# SH6_-_MICROCONTROLLER.net
KiCad netlist of a schematic drawn in Altium Designer
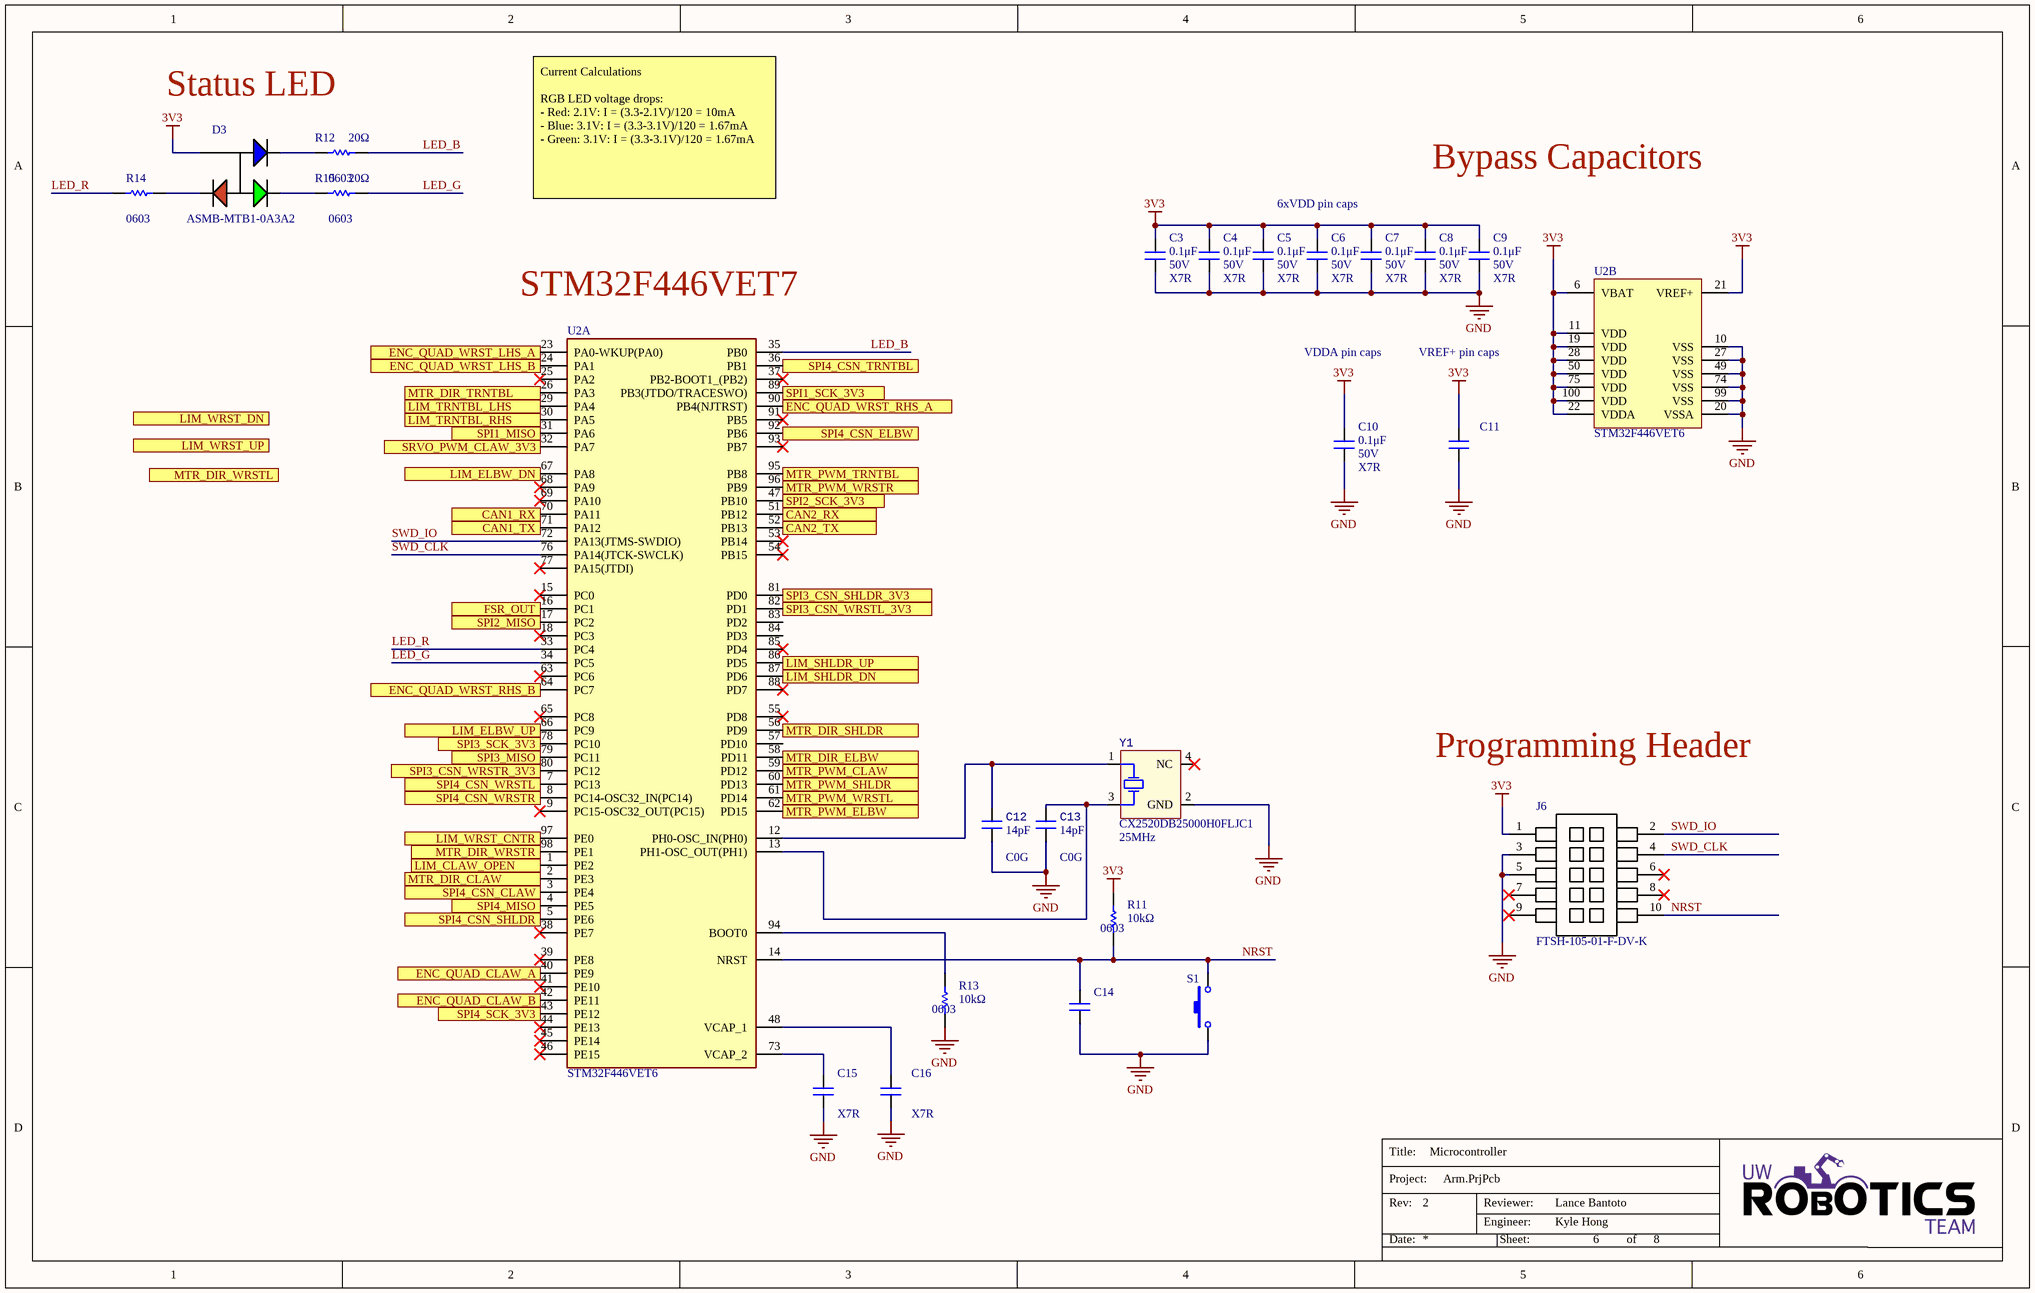
[diagram p0: SH6 - MICROCONTROLLER.SchDoc]

(export (version "E")
  (design (tool "Eeschema 10.0.6"))
  (components
    (comp (ref "C3")
      (value "0.1μF")
      (footprint "CAP0603")
      (description "CAP CER 0.1UF 50V X7R 0603")
      (fields
        (field (name "VOLTAGE RATING") "50V")
        (field (name "DIELECTRIC") "X7R")
        (field (name "Comment") "CAP_0.1uF_50V_0603")
      )
      (libsource (lib "UWRT_Schematic_Library_2020") (part "CAP_0.1uF_50V_0603"))
    )
    (comp (ref "C4")
      (value "0.1μF")
      (footprint "CAP0603")
      (description "CAP CER 0.1UF 50V X7R 0603")
      (fields
        (field (name "VOLTAGE RATING") "50V")
        (field (name "DIELECTRIC") "X7R")
        (field (name "Comment") "CAP_0.1uF_50V_0603")
      )
      (libsource (lib "UWRT_Schematic_Library_2020") (part "CAP_0.1uF_50V_0603"))
    )
    (comp (ref "C5")
      (value "0.1μF")
      (footprint "CAP0603")
      (description "CAP CER 0.1UF 50V X7R 0603")
      (fields
        (field (name "VOLTAGE RATING") "50V")
        (field (name "DIELECTRIC") "X7R")
        (field (name "Comment") "CAP_0.1uF_50V_0603")
      )
      (libsource (lib "UWRT_Schematic_Library_2020") (part "CAP_0.1uF_50V_0603"))
    )
    (comp (ref "C6")
      (value "0.1μF")
      (footprint "CAP0603")
      (description "CAP CER 0.1UF 50V X7R 0603")
      (fields
        (field (name "VOLTAGE RATING") "50V")
        (field (name "DIELECTRIC") "X7R")
        (field (name "Comment") "CAP_0.1uF_50V_0603")
      )
      (libsource (lib "UWRT_Schematic_Library_2020") (part "CAP_0.1uF_50V_0603"))
    )
    (comp (ref "C7")
      (value "0.1μF")
      (footprint "CAP0603")
      (description "CAP CER 0.1UF 50V X7R 0603")
      (fields
        (field (name "VOLTAGE RATING") "50V")
        (field (name "DIELECTRIC") "X7R")
        (field (name "Comment") "CAP_0.1uF_50V_0603")
      )
      (libsource (lib "UWRT_Schematic_Library_2020") (part "CAP_0.1uF_50V_0603"))
    )
    (comp (ref "C8")
      (value "0.1μF")
      (footprint "CAP0603")
      (description "CAP CER 0.1UF 50V X7R 0603")
      (fields
        (field (name "VOLTAGE RATING") "50V")
        (field (name "DIELECTRIC") "X7R")
        (field (name "Comment") "CAP_0.1uF_50V_0603")
      )
      (libsource (lib "UWRT_Schematic_Library_2020") (part "CAP_0.1uF_50V_0603"))
    )
    (comp (ref "C9")
      (value "0.1μF")
      (footprint "CAP0603")
      (description "CAP CER 0.1UF 50V X7R 0603")
      (fields
        (field (name "VOLTAGE RATING") "50V")
        (field (name "DIELECTRIC") "X7R")
        (field (name "Comment") "CAP_0.1uF_50V_0603")
      )
      (libsource (lib "UWRT_Schematic_Library_2020") (part "CAP_0.1uF_50V_0603"))
    )
    (comp (ref "C10")
      (value "0.1μF")
      (footprint "CAP0603")
      (description "CAP CER 0.1UF 50V X7R 0603")
      (fields
        (field (name "VOLTAGE RATING") "50V")
        (field (name "DIELECTRIC") "X7R")
        (field (name "Comment") "CAP_0.1uF_50V_0603")
      )
      (libsource (lib "UWRT_Schematic_Library_2020") (part "CAP_0.1uF_50V_0603"))
    )
    (comp (ref "C11")
      (value "CAP_1uF_25V_0603")
      (footprint "CAP0603")
      (description "CAP CER 1UF 25V X5R 0603")
      (libsource (lib "UWRT_Schematic_Library_2020") (part "CAP_1uF_25V_0603"))
    )
    (comp (ref "C12")
      (value "14pF")
      (footprint "CAP0603")
      (description "CAP CER 14PF 50V C0G/NP0 0603")
      (fields (field (name "DIELECTRIC") "C0G") (field (name "Comment") "CAP_14pF_50V_0603"))
      (libsource (lib "UWRT_Schematic_Library_2020") (part "CAP_14pF_50V_0603"))
    )
    (comp (ref "C13")
      (value "14pF")
      (footprint "CAP0603")
      (description "CAP CER 14PF 50V C0G/NP0 0603")
      (fields (field (name "DIELECTRIC") "C0G") (field (name "Comment") "CAP_14pF_50V_0603"))
      (libsource (lib "UWRT_Schematic_Library_2020") (part "CAP_14pF_50V_0603"))
    )
    (comp (ref "C14")
      (value "CAP_1uF_25V_0603")
      (footprint "CAP0603")
      (description "CAP CER 1UF 25V X5R 0603")
      (libsource (lib "UWRT_Schematic_Library_2020") (part "CAP_1uF_25V_0603"))
    )
    (comp (ref "C15")
      (value "CAP_4.7uF_50V_1206")
      (footprint "CAP1206")
      (description "CAP CER 4.7UF 50V X7R 1206")
      (fields (field (name "DIELECTRIC") "X7R"))
      (libsource (lib "UWRT_Schematic_Library_2020") (part "CAP_4.7uF_50V_1206"))
    )
    (comp (ref "C16")
      (value "CAP_4.7uF_50V_1206")
      (footprint "CAP1206")
      (description "CAP CER 4.7UF 50V X7R 1206")
      (fields (field (name "DIELECTRIC") "X7R"))
      (libsource (lib "UWRT_Schematic_Library_2020") (part "CAP_4.7uF_50V_1206"))
    )
    (comp (ref "D3")
      (value "LED_RGB")
      (footprint "LED_RGB")
      (description "LED RGB DIFFUSED 4PLCC SMD")
      (fields (field (name "MANUFACTURER PART NUMBER 1") "ASMB-MTB1-0A3A2"))
      (libsource (lib "UWRT_Schematic_Library_2020") (part "LED_RGB"))
    )
    (comp (ref "J6")
      (value "CON_PROGRAMMING")
      (footprint "FTSH-105-01-F-DV-K-P-TR")
      (description "CONN HEADER SMD 10POS 1.27MM")
      (fields (field (name "MANUFACTURER PART NUMBER 1") "FTSH-105-01-F-DV-K"))
      (libsource (lib "UWRT_Schematic_Library_2020") (part "CON_PROGRAMMING"))
    )
    (comp (ref "R11")
      (value "10kΩ")
      (footprint "RESC0603")
      (description "RES 10K OHM 5% 1/10W 0603")
      (fields (field (name "PACKAGE/FOOTPRINT") "0603") (field (name "Comment") "RES_10kΩ_0603_5%"))
      (libsource (lib "UWRT_Schematic_Library_2020") (part "RES_10kΩ_0603_5%"))
    )
    (comp (ref "R12")
      (value "20Ω")
      (footprint "RESC0603")
      (description "RES 20 OHM 5% 1/10W 0603")
      (fields (field (name "PACKAGE/FOOTPRINT") "0603") (field (name "Comment") "RES_20Ω_0603_5%"))
      (libsource (lib "UWRT_Schematic_Library_2020") (part "RES_20Ω_0603_5%"))
    )
    (comp (ref "R13")
      (value "10kΩ")
      (footprint "RESC0603")
      (description "RES 10K OHM 5% 1/10W 0603")
      (fields (field (name "PACKAGE/FOOTPRINT") "0603") (field (name "Comment") "RES_10kΩ_0603_5%"))
      (libsource (lib "UWRT_Schematic_Library_2020") (part "RES_10kΩ_0603_5%"))
    )
    (comp (ref "R14")
      (value "RES_120Ω_0603_5%_HP")
      (footprint "RESC0603")
      (description "RES 120 OHM 5% 1/4W 0603")
      (fields (field (name "PACKAGE/FOOTPRINT") "0603"))
      (libsource (lib "UWRT_Schematic_Library_2020") (part "RES_120Ω_0603_5%_HP"))
    )
    (comp (ref "R15")
      (value "20Ω")
      (footprint "RESC0603")
      (description "RES 20 OHM 5% 1/10W 0603")
      (fields (field (name "PACKAGE/FOOTPRINT") "0603") (field (name "Comment") "RES_20Ω_0603_5%"))
      (libsource (lib "UWRT_Schematic_Library_2020") (part "RES_20Ω_0603_5%"))
    )
    (comp (ref "S1")
      (value "SW_TACTILE")
      (footprint "B3U-1000P")
      (description "SWITCH TACTILE SPST-NO 0.05A 12V")
      (libsource (lib "UWRT_Schematic_Library_2020") (part "SW_TACTILE"))
    )
    (comp (ref "U2")
      (value "STM32F446VET6")
      (footprint "STM32F446VET6")
      (description "IC MCU 32BIT 512KB FLASH 100LQFP")
      (libsource (lib "UWRT_Schematic_Library_2020") (part "STM32F446VET6"))
    )
    (comp (ref "Y1")
      (value "CRYSTAL_25MHZ")
      (footprint "SOIC254P1016X440-4N")
      (description "CRYSTAL 25.0000MHZ 12PF SMD")
      (fields
        (field (name "MANUFACTURER PART NUMBER 1") "CX2520DB25000H0FLJC1")
        (field (name "FREQUENCY") "25MHz")
      )
      (libsource (lib "UWRT_Schematic_Library_2020") (part "CRYSTAL_25MHZ"))
    )
  )
  (nets
    (net (code "1") (name "/CAN1_RX") (class "Default")
      (node (ref "U2") (pin "70") (pinfunction "PA11_70") (pintype "passive"))
    )
    (net (code "2") (name "/CAN1_TX") (class "Default")
      (node (ref "U2") (pin "71") (pinfunction "PA12_71") (pintype "passive"))
    )
    (net (code "3") (name "/CAN2_RX") (class "Default")
      (node (ref "U2") (pin "51") (pinfunction "PB12_51") (pintype "passive"))
    )
    (net (code "4") (name "/CAN2_TX") (class "Default")
      (node (ref "U2") (pin "52") (pinfunction "PB13_52") (pintype "passive"))
    )
    (net (code "5") (name "/ENC_QUAD_CLAW_A") (class "Default")
      (node (ref "U2") (pin "40") (pinfunction "PE9_40") (pintype "passive"))
    )
    (net (code "6") (name "/ENC_QUAD_CLAW_B") (class "Default")
      (node (ref "U2") (pin "42") (pinfunction "PE11_42") (pintype "passive"))
    )
    (net (code "7") (name "/ENC_QUAD_WRST_LHS_A") (class "Default")
      (node (ref "U2") (pin "23") (pinfunction "PA0-WKUP(PA0)_23") (pintype "passive"))
    )
    (net (code "8") (name "/ENC_QUAD_WRST_LHS_B") (class "Default")
      (node (ref "U2") (pin "24") (pinfunction "PA1_24") (pintype "passive"))
    )
    (net (code "9") (name "/ENC_QUAD_WRST_RHS_A") (class "Default")
      (node (ref "U2") (pin "90") (pinfunction "PB4(NJTRST)_90") (pintype "passive"))
    )
    (net (code "10") (name "/ENC_QUAD_WRST_RHS_B") (class "Default")
      (node (ref "U2") (pin "64") (pinfunction "PC7_64") (pintype "passive"))
    )
    (net (code "11") (name "/FSR_OUT") (class "Default")
      (node (ref "U2") (pin "16") (pinfunction "PC1_16") (pintype "passive"))
    )
    (net (code "12") (name "/LED_B") (class "Default")
      (node (ref "R12") (pin "2") (pinfunction "2_2") (pintype "passive"))
      (node (ref "U2") (pin "35") (pinfunction "PB0_35") (pintype "passive"))
    )
    (net (code "13") (name "/LED_G") (class "Default")
      (node (ref "R15") (pin "2") (pinfunction "2_2") (pintype "passive"))
      (node (ref "U2") (pin "34") (pinfunction "PC5_34") (pintype "passive"))
    )
    (net (code "14") (name "/LED_R") (class "Default")
      (node (ref "R14") (pin "1") (pinfunction "1_1") (pintype "passive"))
      (node (ref "U2") (pin "33") (pinfunction "PC4_33") (pintype "passive"))
    )
    (net (code "15") (name "/LIM_CLAW_OPEN") (class "Default")
      (node (ref "U2") (pin "1") (pinfunction "PE2_1") (pintype "passive"))
    )
    (net (code "16") (name "/LIM_ELBW_DN") (class "Default")
      (node (ref "U2") (pin "67") (pinfunction "PA8_67") (pintype "passive"))
    )
    (net (code "17") (name "/LIM_ELBW_UP") (class "Default")
      (node (ref "U2") (pin "66") (pinfunction "PC9_66") (pintype "passive"))
    )
    (net (code "18") (name "/LIM_SHLDR_DN") (class "Default")
      (node (ref "U2") (pin "87") (pinfunction "PD6_87") (pintype "passive"))
    )
    (net (code "19") (name "/LIM_SHLDR_UP") (class "Default")
      (node (ref "U2") (pin "86") (pinfunction "PD5_86") (pintype "passive"))
    )
    (net (code "20") (name "/LIM_TRNTBL_LHS") (class "Default")
      (node (ref "U2") (pin "29") (pinfunction "PA4_29") (pintype "passive"))
    )
    (net (code "21") (name "/LIM_TRNTBL_RHS") (class "Default")
      (node (ref "U2") (pin "30") (pinfunction "PA5_30") (pintype "passive"))
    )
    (net (code "22") (name "/LIM_WRST_CNTR") (class "Default")
      (node (ref "U2") (pin "97") (pinfunction "PE0_97") (pintype "passive"))
    )
    (net (code "25") (name "/MTR_DIR_CLAW") (class "Default")
      (node (ref "U2") (pin "2") (pinfunction "PE3_2") (pintype "passive"))
    )
    (net (code "26") (name "/MTR_DIR_ELBW") (class "Default")
      (node (ref "U2") (pin "58") (pinfunction "PD11_58") (pintype "passive"))
    )
    (net (code "27") (name "/MTR_DIR_SHLDR") (class "Default")
      (node (ref "U2") (pin "56") (pinfunction "PD9_56") (pintype "passive"))
    )
    (net (code "28") (name "/MTR_DIR_TRNTBL") (class "Default")
      (node (ref "U2") (pin "26") (pinfunction "PA3_26") (pintype "passive"))
    )
    (net (code "30") (name "/MTR_DIR_WRSTR") (class "Default")
      (node (ref "U2") (pin "98") (pinfunction "PE1_98") (pintype "passive"))
    )
    (net (code "31") (name "/MTR_PWM_CLAW") (class "Default")
      (node (ref "U2") (pin "59") (pinfunction "PD12_59") (pintype "passive"))
    )
    (net (code "32") (name "/MTR_PWM_ELBW") (class "Default")
      (node (ref "U2") (pin "62") (pinfunction "PD15_62") (pintype "passive"))
    )
    (net (code "33") (name "/MTR_PWM_SHLDR") (class "Default")
      (node (ref "U2") (pin "60") (pinfunction "PD13_60") (pintype "passive"))
    )
    (net (code "34") (name "/MTR_PWM_TRNTBL") (class "Default")
      (node (ref "U2") (pin "95") (pinfunction "PB8_95") (pintype "passive"))
    )
    (net (code "35") (name "/MTR_PWM_WRSTL") (class "Default")
      (node (ref "U2") (pin "61") (pinfunction "PD14_61") (pintype "passive"))
    )
    (net (code "36") (name "/MTR_PWM_WRSTR") (class "Default")
      (node (ref "U2") (pin "96") (pinfunction "PB9_96") (pintype "passive"))
    )
    (net (code "37") (name "/NRST") (class "Default")
      (node (ref "C14") (pin "2") (pinfunction "2_2") (pintype "passive"))
      (node (ref "J6") (pin "10") (pinfunction "10_10") (pintype "passive"))
      (node (ref "R11") (pin "2") (pinfunction "2_2") (pintype "passive"))
      (node (ref "S1") (pin "2") (pinfunction "2_2") (pintype "passive"))
      (node (ref "U2") (pin "14") (pinfunction "NRST_14") (pintype "passive"))
    )
    (net (code "38") (name "/SPI1_MISO") (class "Default")
      (node (ref "U2") (pin "31") (pinfunction "PA6_31") (pintype "passive"))
    )
    (net (code "39") (name "/SPI1_SCK_3V3") (class "Default")
      (node (ref "U2") (pin "89") (pinfunction "PB3(JTDO/TRACESWO)_89") (pintype "passive"))
    )
    (net (code "40") (name "/SPI2_MISO") (class "Default")
      (node (ref "U2") (pin "17") (pinfunction "PC2_17") (pintype "passive"))
    )
    (net (code "41") (name "/SPI2_SCK_3V3") (class "Default")
      (node (ref "U2") (pin "47") (pinfunction "PB10_47") (pintype "passive"))
    )
    (net (code "42") (name "/SPI3_CSN_SHLDR_3V3") (class "Default")
      (node (ref "U2") (pin "81") (pinfunction "PD0_81") (pintype "passive"))
    )
    (net (code "43") (name "/SPI3_CSN_WRSTL_3V3") (class "Default")
      (node (ref "U2") (pin "82") (pinfunction "PD1_82") (pintype "passive"))
    )
    (net (code "44") (name "/SPI3_CSN_WRSTR_3V3") (class "Default")
      (node (ref "U2") (pin "80") (pinfunction "PC12_80") (pintype "passive"))
    )
    (net (code "45") (name "/SPI3_MISO") (class "Default")
      (node (ref "U2") (pin "79") (pinfunction "PC11_79") (pintype "passive"))
    )
    (net (code "46") (name "/SPI3_SCK_3V3") (class "Default")
      (node (ref "U2") (pin "78") (pinfunction "PC10_78") (pintype "passive"))
    )
    (net (code "47") (name "/SPI4_CSN_CLAW") (class "Default")
      (node (ref "U2") (pin "3") (pinfunction "PE4_3") (pintype "passive"))
    )
    (net (code "48") (name "/SPI4_CSN_ELBW") (class "Default")
      (node (ref "U2") (pin "92") (pinfunction "PB6_92") (pintype "passive"))
    )
    (net (code "49") (name "/SPI4_CSN_SHLDR") (class "Default")
      (node (ref "U2") (pin "5") (pinfunction "PE6_5") (pintype "passive"))
    )
    (net (code "50") (name "/SPI4_CSN_TRNTBL") (class "Default")
      (node (ref "U2") (pin "36") (pinfunction "PB1_36") (pintype "passive"))
    )
    (net (code "51") (name "/SPI4_CSN_WRSTL") (class "Default")
      (node (ref "U2") (pin "7") (pinfunction "PC13_7") (pintype "passive"))
    )
    (net (code "52") (name "/SPI4_CSN_WRSTR") (class "Default")
      (node (ref "U2") (pin "8") (pinfunction "PC14-OSC32_IN(PC14)_8") (pintype "passive"))
    )
    (net (code "53") (name "/SPI4_MISO") (class "Default")
      (node (ref "U2") (pin "4") (pinfunction "PE5_4") (pintype "passive"))
    )
    (net (code "54") (name "/SPI4_SCK_3V3") (class "Default")
      (node (ref "U2") (pin "43") (pinfunction "PE12_43") (pintype "passive"))
    )
    (net (code "55") (name "/SRVO_PWM_CLAW_3V3") (class "Default")
      (node (ref "U2") (pin "32") (pinfunction "PA7_32") (pintype "passive"))
    )
    (net (code "56") (name "/SWD_CLK") (class "Default")
      (node (ref "J6") (pin "4") (pinfunction "4_4") (pintype "passive"))
      (node (ref "U2") (pin "76") (pinfunction "PA14(JTCK-SWCLK)_76") (pintype "passive"))
    )
    (net (code "57") (name "/SWD_IO") (class "Default")
      (node (ref "J6") (pin "2") (pinfunction "2_2") (pintype "passive"))
      (node (ref "U2") (pin "72") (pinfunction "PA13(JTMS-SWDIO)_72") (pintype "passive"))
    )
    (net (code "58") (name "3V3") (class "Default")
      (node (ref "C10") (pin "2") (pinfunction "2_2") (pintype "passive"))
      (node (ref "C11") (pin "2") (pinfunction "2_2") (pintype "passive"))
      (node (ref "C3") (pin "1") (pinfunction "1_1") (pintype "passive"))
      (node (ref "C4") (pin "1") (pinfunction "1_1") (pintype "passive"))
      (node (ref "C5") (pin "1") (pinfunction "1_1") (pintype "passive"))
      (node (ref "C6") (pin "1") (pinfunction "1_1") (pintype "passive"))
      (node (ref "C7") (pin "1") (pinfunction "1_1") (pintype "passive"))
      (node (ref "C8") (pin "1") (pinfunction "1_1") (pintype "passive"))
      (node (ref "C9") (pin "1") (pinfunction "1_1") (pintype "passive"))
      (node (ref "D3") (pin "4") (pinfunction "COMMON_ANODE_4") (pintype "passive"))
      (node (ref "J6") (pin "1") (pinfunction "1_1") (pintype "passive"))
      (node (ref "R11") (pin "1") (pinfunction "1_1") (pintype "passive"))
      (node (ref "U2") (pin "100") (pinfunction "VDD_100") (pintype "passive"))
      (node (ref "U2") (pin "11") (pinfunction "VDD_11") (pintype "passive"))
      (node (ref "U2") (pin "19") (pinfunction "VDD_19") (pintype "passive"))
      (node (ref "U2") (pin "21") (pinfunction "VREF+_21") (pintype "passive"))
      (node (ref "U2") (pin "22") (pinfunction "VDDA_22") (pintype "passive"))
      (node (ref "U2") (pin "28") (pinfunction "VDD_28") (pintype "passive"))
      (node (ref "U2") (pin "50") (pinfunction "VDD_50") (pintype "passive"))
      (node (ref "U2") (pin "6") (pinfunction "VBAT_6") (pintype "passive"))
      (node (ref "U2") (pin "75") (pinfunction "VDD_75") (pintype "passive"))
    )
    (net (code "59") (name "GND") (class "Default")
      (node (ref "C10") (pin "1") (pinfunction "1_1") (pintype "passive"))
      (node (ref "C11") (pin "1") (pinfunction "1_1") (pintype "passive"))
      (node (ref "C12") (pin "1") (pinfunction "1_1") (pintype "passive"))
      (node (ref "C13") (pin "1") (pinfunction "1_1") (pintype "passive"))
      (node (ref "C14") (pin "1") (pinfunction "1_1") (pintype "passive"))
      (node (ref "C15") (pin "1") (pinfunction "1_1") (pintype "passive"))
      (node (ref "C16") (pin "1") (pinfunction "1_1") (pintype "passive"))
      (node (ref "C3") (pin "2") (pinfunction "2_2") (pintype "passive"))
      (node (ref "C4") (pin "2") (pinfunction "2_2") (pintype "passive"))
      (node (ref "C5") (pin "2") (pinfunction "2_2") (pintype "passive"))
      (node (ref "C6") (pin "2") (pinfunction "2_2") (pintype "passive"))
      (node (ref "C7") (pin "2") (pinfunction "2_2") (pintype "passive"))
      (node (ref "C8") (pin "2") (pinfunction "2_2") (pintype "passive"))
      (node (ref "C9") (pin "2") (pinfunction "2_2") (pintype "passive"))
      (node (ref "J6") (pin "3") (pinfunction "3_3") (pintype "passive"))
      (node (ref "J6") (pin "5") (pinfunction "5_5") (pintype "passive"))
      (node (ref "R13") (pin "2") (pinfunction "2_2") (pintype "passive"))
      (node (ref "S1") (pin "1") (pinfunction "1_1") (pintype "passive"))
      (node (ref "U2") (pin "10") (pinfunction "VSS_10") (pintype "passive"))
      (node (ref "U2") (pin "20") (pinfunction "VSSA_20") (pintype "passive"))
      (node (ref "U2") (pin "27") (pinfunction "VSS_27") (pintype "passive"))
      (node (ref "U2") (pin "49") (pinfunction "VSS_49") (pintype "passive"))
      (node (ref "U2") (pin "74") (pinfunction "VSS_74") (pintype "passive"))
      (node (ref "U2") (pin "99") (pinfunction "VSS_99") (pintype "passive"))
      (node (ref "Y1") (pin "2") (pinfunction "GND_2") (pintype "power_in"))
    )
    (net (code "60") (name "Net-(D3-CATHODE_(BLUE))") (class "Default")
      (node (ref "D3") (pin "3") (pinfunction "CATHODE_(BLUE)_3") (pintype "passive"))
      (node (ref "R12") (pin "1") (pinfunction "1_1") (pintype "passive"))
    )
    (net (code "61") (name "Net-(D3-CATHODE_(GREEN))") (class "Default")
      (node (ref "D3") (pin "2") (pinfunction "CATHODE_(GREEN)_2") (pintype "passive"))
      (node (ref "R15") (pin "1") (pinfunction "1_1") (pintype "passive"))
    )
    (net (code "62") (name "Net-(D3-CATHODE_(RED))") (class "Default")
      (node (ref "D3") (pin "1") (pinfunction "CATHODE_(RED)_1") (pintype "passive"))
      (node (ref "R14") (pin "2") (pinfunction "2_2") (pintype "passive"))
    )
    (net (code "63") (name "Net-(U2A-BOOT0)") (class "Default")
      (node (ref "R13") (pin "1") (pinfunction "1_1") (pintype "passive"))
      (node (ref "U2") (pin "94") (pinfunction "BOOT0_94") (pintype "passive"))
    )
    (net (code "64") (name "Net-(U2A-PH0-OSC_IN(PH0))") (class "Default")
      (node (ref "C12") (pin "2") (pinfunction "2_2") (pintype "passive"))
      (node (ref "U2") (pin "12") (pinfunction "PH0-OSC_IN(PH0)_12") (pintype "passive"))
      (node (ref "Y1") (pin "1") (pinfunction "HOT_1") (pintype "passive"))
    )
    (net (code "65") (name "Net-(U2A-PH1-OSC_OUT(PH1))") (class "Default")
      (node (ref "C13") (pin "2") (pinfunction "2_2") (pintype "passive"))
      (node (ref "U2") (pin "13") (pinfunction "PH1-OSC_OUT(PH1)_13") (pintype "passive"))
      (node (ref "Y1") (pin "3") (pinfunction "HOT_3") (pintype "passive"))
    )
    (net (code "66") (name "Net-(U2A-VCAP_1)") (class "Default")
      (node (ref "C16") (pin "2") (pinfunction "2_2") (pintype "passive"))
      (node (ref "U2") (pin "48") (pinfunction "VCAP_1_48") (pintype "passive"))
    )
    (net (code "67") (name "Net-(U2A-VCAP_2)") (class "Default")
      (node (ref "C15") (pin "2") (pinfunction "2_2") (pintype "passive"))
      (node (ref "U2") (pin "73") (pinfunction "VCAP_2_73") (pintype "passive"))
    )
    (net (code "68") (name "unconnected-(J6-Pad6)") (class "Default")
      (node (ref "J6") (pin "6") (pinfunction "6_6") (pintype "passive+no_connect"))
    )
    (net (code "69") (name "unconnected-(J6-Pad7)") (class "Default")
      (node (ref "J6") (pin "7") (pinfunction "7_7") (pintype "passive+no_connect"))
    )
    (net (code "70") (name "unconnected-(J6-Pad8)") (class "Default")
      (node (ref "J6") (pin "8") (pinfunction "8_8") (pintype "passive+no_connect"))
    )
    (net (code "71") (name "unconnected-(J6-Pad9)") (class "Default")
      (node (ref "J6") (pin "9") (pinfunction "9_9") (pintype "passive+no_connect"))
    )
    (net (code "72") (name "unconnected-(U2A-PA2-Pad25)") (class "Default")
      (node (ref "U2") (pin "25") (pinfunction "PA2_25") (pintype "passive+no_connect"))
    )
    (net (code "73") (name "unconnected-(U2A-PA9-Pad68)") (class "Default")
      (node (ref "U2") (pin "68") (pinfunction "PA9_68") (pintype "passive+no_connect"))
    )
    (net (code "74") (name "unconnected-(U2A-PA10-Pad69)") (class "Default")
      (node (ref "U2") (pin "69") (pinfunction "PA10_69") (pintype "passive+no_connect"))
    )
    (net (code "75") (name "unconnected-(U2A-PA15(JTDI)-Pad77)") (class "Default")
      (node (ref "U2") (pin "77") (pinfunction "PA15(JTDI)_77") (pintype "passive+no_connect"))
    )
    (net (code "76") (name "unconnected-(U2A-PB2-BOOT1_(PB2)-Pad37)") (class "Default")
      (node (ref "U2") (pin "37") (pinfunction "PB2-BOOT1_(PB2)_37") (pintype "passive+no_connect"))
    )
    (net (code "77") (name "unconnected-(U2A-PB5-Pad91)") (class "Default")
      (node (ref "U2") (pin "91") (pinfunction "PB5_91") (pintype "passive+no_connect"))
    )
    (net (code "78") (name "unconnected-(U2A-PB7-Pad93)") (class "Default")
      (node (ref "U2") (pin "93") (pinfunction "PB7_93") (pintype "passive+no_connect"))
    )
    (net (code "79") (name "unconnected-(U2A-PB14-Pad53)") (class "Default")
      (node (ref "U2") (pin "53") (pinfunction "PB14_53") (pintype "passive+no_connect"))
    )
    (net (code "80") (name "unconnected-(U2A-PB15-Pad54)") (class "Default")
      (node (ref "U2") (pin "54") (pinfunction "PB15_54") (pintype "passive+no_connect"))
    )
    (net (code "81") (name "unconnected-(U2A-PC0-Pad15)") (class "Default")
      (node (ref "U2") (pin "15") (pinfunction "PC0_15") (pintype "passive+no_connect"))
    )
    (net (code "82") (name "unconnected-(U2A-PC3-Pad18)") (class "Default")
      (node (ref "U2") (pin "18") (pinfunction "PC3_18") (pintype "passive+no_connect"))
    )
    (net (code "83") (name "unconnected-(U2A-PC6-Pad63)") (class "Default")
      (node (ref "U2") (pin "63") (pinfunction "PC6_63") (pintype "passive+no_connect"))
    )
    (net (code "84") (name "unconnected-(U2A-PC8-Pad65)") (class "Default")
      (node (ref "U2") (pin "65") (pinfunction "PC8_65") (pintype "passive+no_connect"))
    )
    (net (code "85") (name "unconnected-(U2A-PC15-OSC32_OUT(PC15)-Pad9)") (class "Default")
      (node (ref "U2") (pin "9") (pinfunction "PC15-OSC32_OUT(PC15)_9") (pintype "passive+no_connect"))
    )
    (net (code "86") (name "unconnected-(U2A-PD2-Pad83)") (class "Default")
      (node (ref "U2") (pin "83") (pinfunction "PD2_83") (pintype "passive"))
    )
    (net (code "87") (name "unconnected-(U2A-PD3-Pad84)") (class "Default")
      (node (ref "U2") (pin "84") (pinfunction "PD3_84") (pintype "passive"))
    )
    (net (code "88") (name "unconnected-(U2A-PD4-Pad85)") (class "Default")
      (node (ref "U2") (pin "85") (pinfunction "PD4_85") (pintype "passive+no_connect"))
    )
    (net (code "89") (name "unconnected-(U2A-PD7-Pad88)") (class "Default")
      (node (ref "U2") (pin "88") (pinfunction "PD7_88") (pintype "passive+no_connect"))
    )
    (net (code "90") (name "unconnected-(U2A-PD8-Pad55)") (class "Default")
      (node (ref "U2") (pin "55") (pinfunction "PD8_55") (pintype "passive+no_connect"))
    )
    (net (code "91") (name "unconnected-(U2A-PD10-Pad57)") (class "Default")
      (node (ref "U2") (pin "57") (pinfunction "PD10_57") (pintype "passive"))
    )
    (net (code "92") (name "unconnected-(U2A-PE7-Pad38)") (class "Default")
      (node (ref "U2") (pin "38") (pinfunction "PE7_38") (pintype "passive+no_connect"))
    )
    (net (code "93") (name "unconnected-(U2A-PE8-Pad39)") (class "Default")
      (node (ref "U2") (pin "39") (pinfunction "PE8_39") (pintype "passive+no_connect"))
    )
    (net (code "94") (name "unconnected-(U2A-PE10-Pad41)") (class "Default")
      (node (ref "U2") (pin "41") (pinfunction "PE10_41") (pintype "passive+no_connect"))
    )
    (net (code "95") (name "unconnected-(U2A-PE13-Pad44)") (class "Default")
      (node (ref "U2") (pin "44") (pinfunction "PE13_44") (pintype "passive+no_connect"))
    )
    (net (code "96") (name "unconnected-(U2A-PE14-Pad45)") (class "Default")
      (node (ref "U2") (pin "45") (pinfunction "PE14_45") (pintype "passive+no_connect"))
    )
    (net (code "97") (name "unconnected-(U2A-PE15-Pad46)") (class "Default")
      (node (ref "U2") (pin "46") (pinfunction "PE15_46") (pintype "passive+no_connect"))
    )
    (net (code "98") (name "unconnected-(Y1-NC-Pad4)") (class "Default")
      (node (ref "Y1") (pin "4") (pinfunction "NC_4") (pintype "passive+no_connect"))
    )
  )
)
